# MCU_Schematic_Winterbreak.net
KiCad netlist of a schematic drawn in Altium Designer
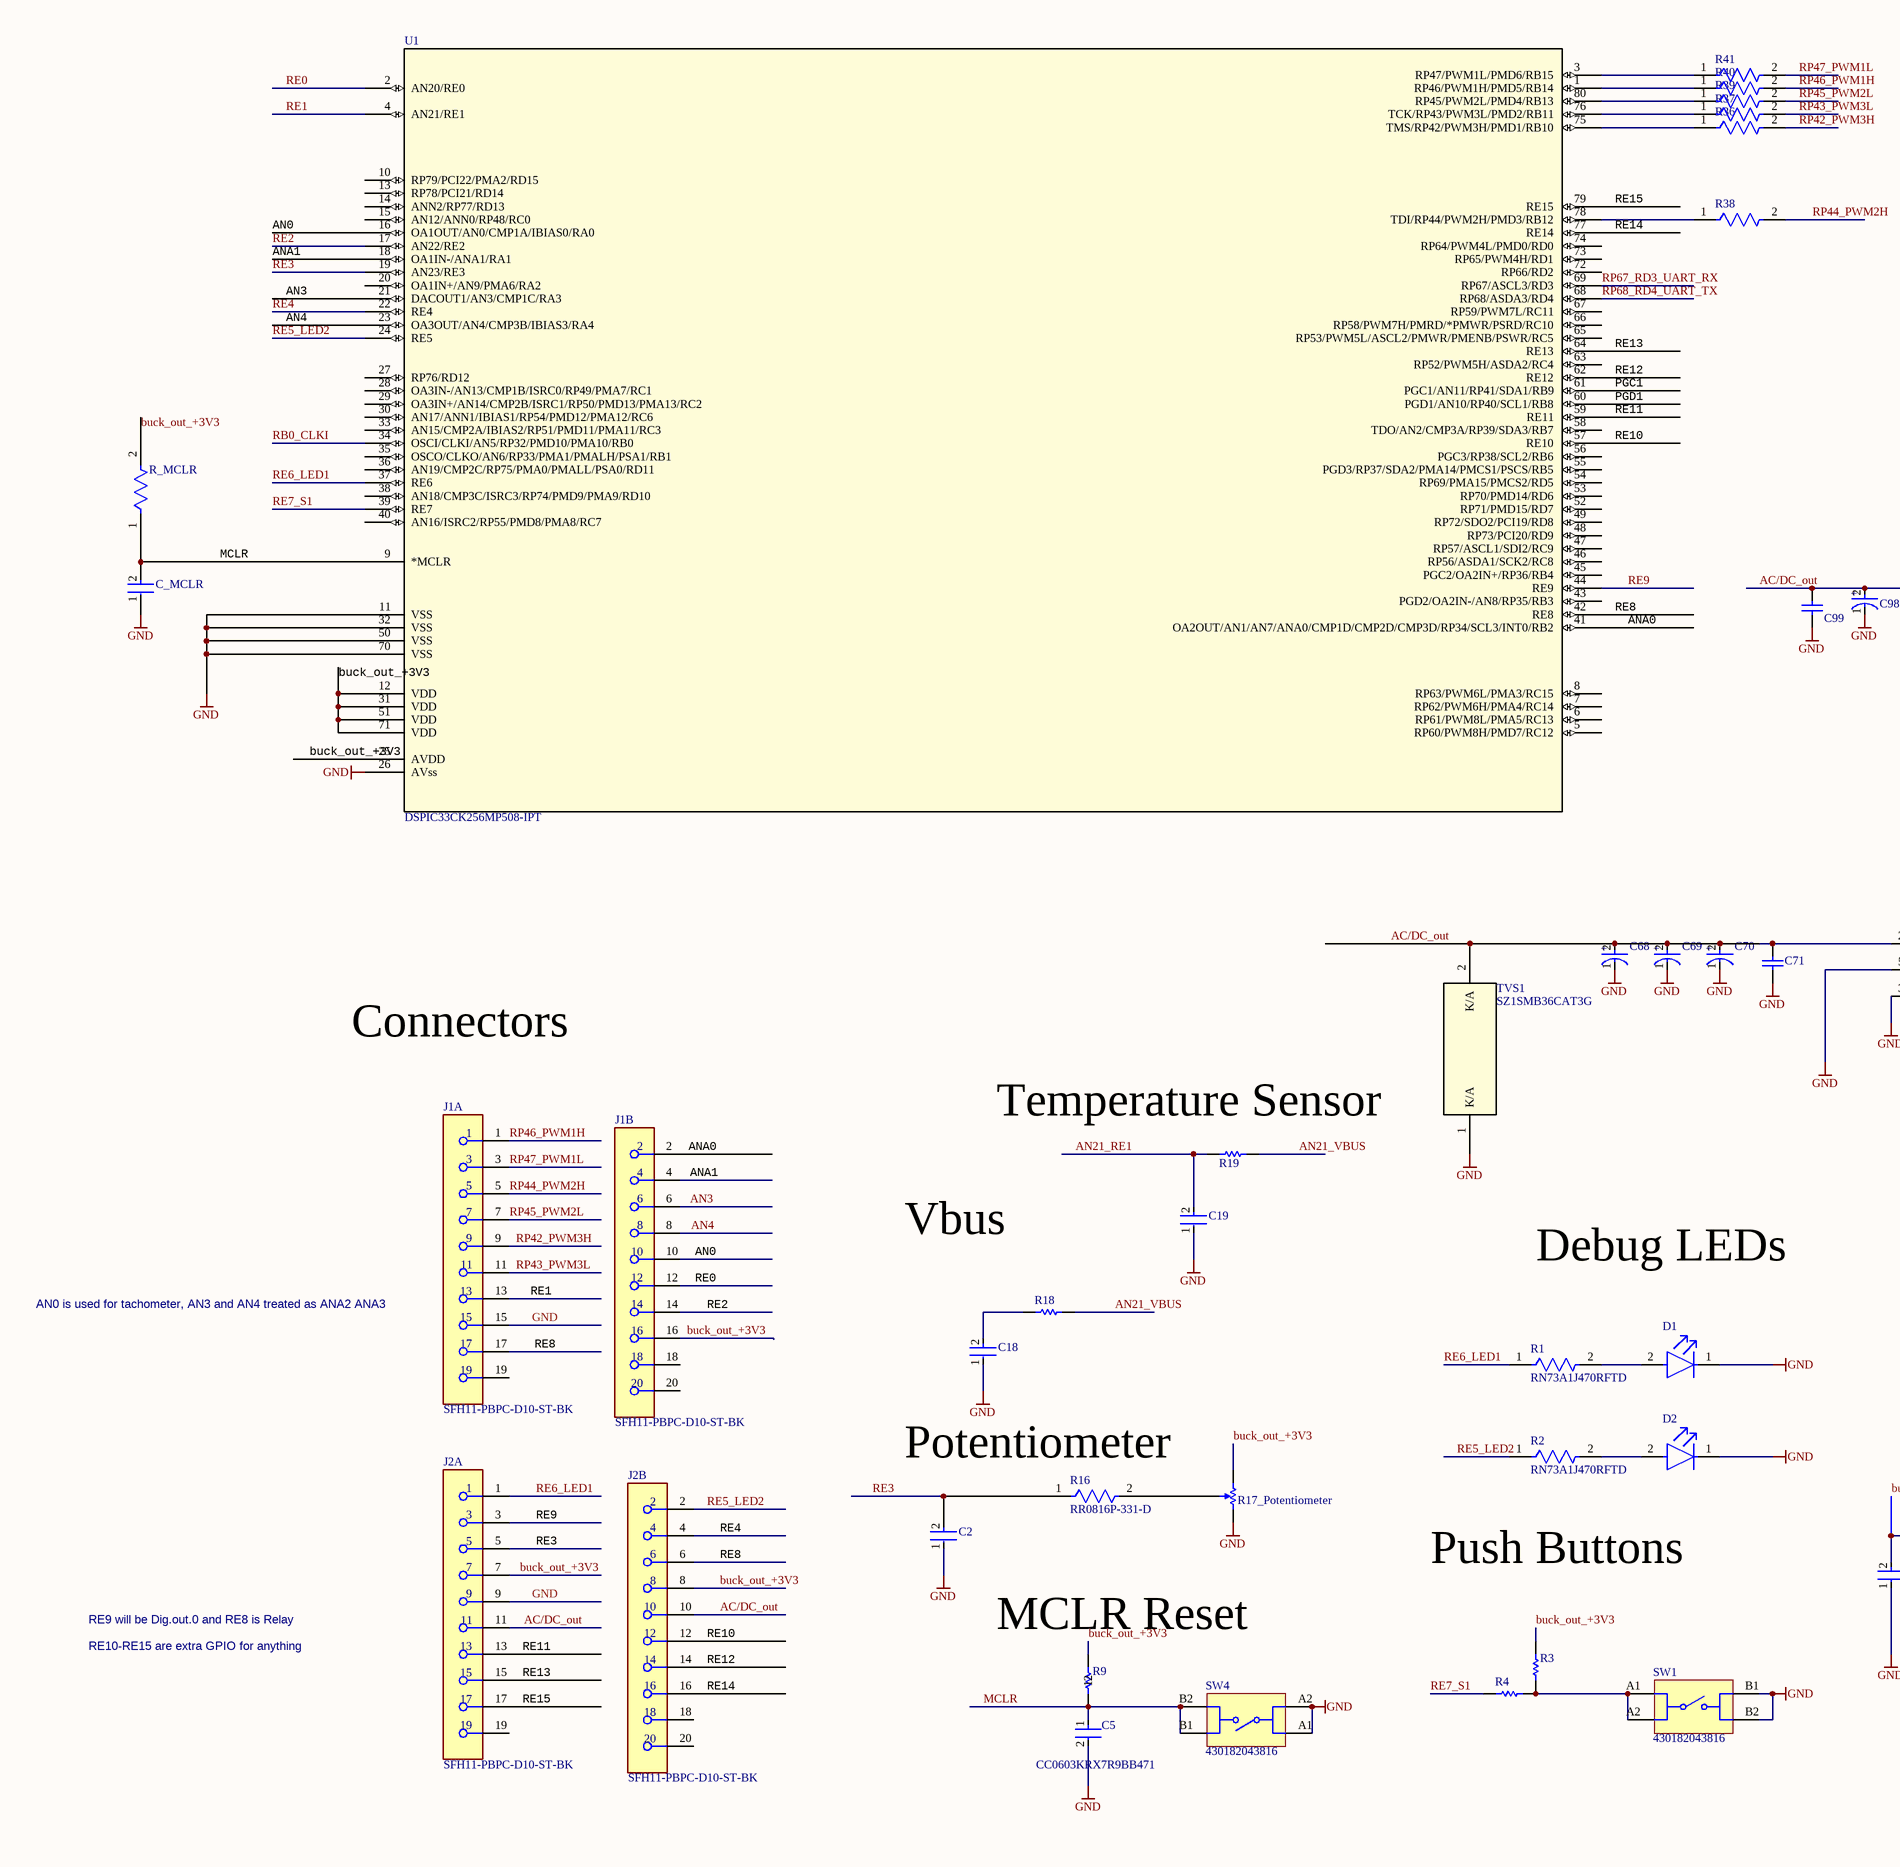
[diagram p0: MCU_Schematic_Winterbreak.SchDoc, left]
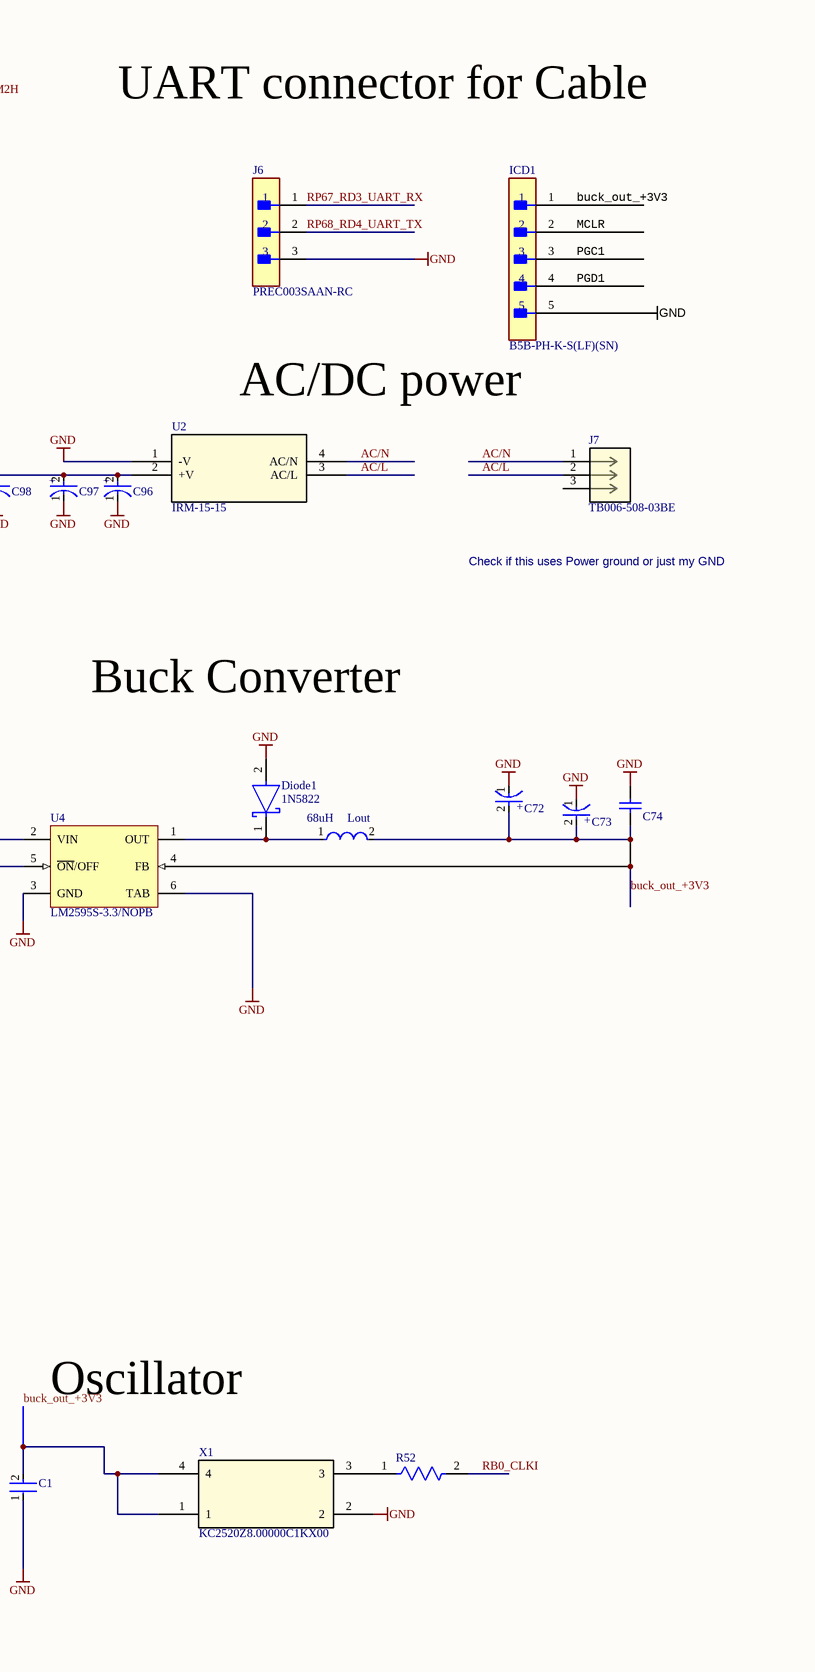
[diagram p1: MCU_Schematic_Winterbreak.SchDoc, right]

(export (version "E")
  (design (tool "Eeschema 10.0.6"))
  (components
    (comp (ref "C1")
      (value "GRM155R71C104KA88D")
      (footprint "FP-GRM15-MFG")
      (description "CAP CER 0.1UF 16V X7R 0402")
      (fields
        (field (name "TOLERANCE") "10%")
        (field (name "OCTOPART") "https://octopart.com/grm155r71c104ka88d-murata-196880")
      )
      (libsource (lib "Altium Content Vault") (part "236180d848d6139a670b325ea6854c9"))
    )
    (comp (ref "C2")
      (value "GRM155R71C104KA88D")
      (footprint "FP-GRM15-MFG")
      (description "CAP CER 0.1UF 16V X7R 0402")
      (fields
        (field (name "TOLERANCE") "10%")
        (field (name "OCTOPART") "https://octopart.com/grm155r71c104ka88d-murata-196880")
      )
      (libsource (lib "Altium Content Vault") (part "236180d848d6139a670b325ea6854c9"))
    )
    (comp (ref "C5")
      (value "CC0603KRX7R9BB471")
      (footprint "FP-CC0603-DA-MFG")
      (description "CAP CER 470PF 50V X7R 0603")
      (fields
        (field (name "VOLTAGE") "50 V")
        (field (name "OCTOPART") "https://octopart.com/cc0603krx7r9bb471-yageo-192931")
      )
      (libsource (lib "Altium Content Vault") (part "11868f565c42a9108669ba33697ecf6"))
    )
    (comp (ref "C18")
      (value "GRM155R71C104KA88D")
      (footprint "FP-GRM15-MFG")
      (description "CAP CER 0.1UF 16V X7R 0402")
      (fields
        (field (name "TOLERANCE") "10%")
        (field (name "OCTOPART") "https://octopart.com/grm155r71c104ka88d-murata-196880")
      )
      (libsource (lib "Altium Content Vault") (part "236180d848d6139a670b325ea6854c9"))
    )
    (comp (ref "C19")
      (value "GRM155R71C104KA88D")
      (footprint "FP-GRM15-MFG")
      (description "CAP CER 0.1UF 16V X7R 0402")
      (fields
        (field (name "TOLERANCE") "10%")
        (field (name "OCTOPART") "https://octopart.com/grm155r71c104ka88d-murata-196880")
      )
      (libsource (lib "Altium Content Vault") (part "236180d848d6139a670b325ea6854c9"))
    )
    (comp (ref "C68")
      (value "EEHAZS1H221B")
      (footprint "FP-EEHA-G16-MFG")
      (description "Conductive Polymer Hybrid Aluminum Electrolytic Capacitors 220uF ±20% 50V RADIAL TH 10x15.7mm")
      (libsource (lib "Altium Content Vault") (part "203bc49f2ac43e59fd269a8c329ed05"))
    )
    (comp (ref "C69")
      (value "EEHAZS1H221B")
      (footprint "FP-EEHA-G16-MFG")
      (description "Conductive Polymer Hybrid Aluminum Electrolytic Capacitors 220uF ±20% 50V RADIAL TH 10x15.7mm")
      (libsource (lib "Altium Content Vault") (part "203bc49f2ac43e59fd269a8c329ed05"))
    )
    (comp (ref "C70")
      (value "TAJE476K035RNJ")
      (footprint "FP-TAJE-MFG")
      (description "47uF 35V  ±10% 900mΩ 2917  SMD Tantalum Capacitor")
      (fields (field (name "VOLTAGE") "35V") (field (name "TOLERANCE") "10%"))
      (libsource (lib "Altium Content Vault") (part "203bc49f2ac43e59fd269a8c329ed05"))
    )
    (comp (ref "C71")
      (value "08055C104KAZ2A")
      (footprint "CAPC2013X94X50NL20T25")
      (fields (field (name "MANUFACTURER") "AVX Interconnect / Elco"))
      (libsource (lib "Altium Content Vault") (part "CAP"))
    )
    (comp (ref "C72")
      (value "EEHAZS1H221B")
      (footprint "FP-EEHA-G16-MFG")
      (description "Conductive Polymer Hybrid Aluminum Electrolytic Capacitors 220uF ±20% 50V RADIAL TH 10x15.7mm")
      (libsource (lib "Altium Content Vault") (part "203bc49f2ac43e59fd269a8c329ed05"))
    )
    (comp (ref "C73")
      (value "TAJE476K035RNJ")
      (footprint "FP-TAJE-MFG")
      (description "47uF 35V  ±10% 900mΩ 2917  SMD Tantalum Capacitor")
      (fields (field (name "VOLTAGE") "35V") (field (name "TOLERANCE") "10%"))
      (libsource (lib "Altium Content Vault") (part "203bc49f2ac43e59fd269a8c329ed05"))
    )
    (comp (ref "C74")
      (value "08055C104KAZ2A")
      (footprint "CAPC2013X94X50NL20T25")
      (fields (field (name "MANUFACTURER") "AVX Interconnect / Elco"))
      (libsource (lib "Altium Content Vault") (part "CAP"))
    )
    (comp (ref "C96")
      (value "EEHAZS1H221B")
      (footprint "FP-EEHA-G16-MFG")
      (description "Conductive Polymer Hybrid Aluminum Electrolytic Capacitors 220uF ±20% 50V RADIAL TH 10x15.7mm")
      (libsource (lib "Altium Content Vault") (part "203bc49f2ac43e59fd269a8c329ed05"))
    )
    (comp (ref "C97")
      (value "EEHAZS1H221B")
      (footprint "FP-EEHA-G16-MFG")
      (description "Conductive Polymer Hybrid Aluminum Electrolytic Capacitors 220uF ±20% 50V RADIAL TH 10x15.7mm")
      (libsource (lib "Altium Content Vault") (part "203bc49f2ac43e59fd269a8c329ed05"))
    )
    (comp (ref "C98")
      (value "TAJE476K035RNJ")
      (footprint "FP-TAJE-MFG")
      (description "47uF 35V  ±10% 900mΩ 2917  SMD Tantalum Capacitor")
      (fields (field (name "VOLTAGE") "35V") (field (name "TOLERANCE") "10%"))
      (libsource (lib "Altium Content Vault") (part "203bc49f2ac43e59fd269a8c329ed05"))
    )
    (comp (ref "C99")
      (value "08055C104KAZ2A")
      (footprint "CAPC2013X94X50NL20T25")
      (fields (field (name "MANUFACTURER") "AVX Interconnect / Elco"))
      (libsource (lib "Altium Content Vault") (part "CAP"))
    )
    (comp (ref "C_MCLR")
      (value "GRM155R71C104KA88D")
      (footprint "FP-GRM15-MFG")
      (description "CAP CER 0.1UF 16V X7R 0402")
      (fields
        (field (name "TOLERANCE") "10%")
        (field (name "OCTOPART") "https://octopart.com/grm155r71c104ka88d-murata-196880")
      )
      (libsource (lib "Altium Content Vault") (part "236180d848d6139a670b325ea6854c9"))
    )
    (comp (ref "D1")
      (value "LTST-C190KGKT")
      (footprint "FP-LTST-C190KGKT-MFG")
      (description "LED GREEN CLEAR CHIP SMD")
      (libsource (lib "Altium Content Vault") (part "8706943c75ba83719d021d2fdc84c58"))
    )
    (comp (ref "D2")
      (value "LTST-C190KGKT")
      (footprint "FP-LTST-C190KGKT-MFG")
      (description "LED GREEN CLEAR CHIP SMD")
      (libsource (lib "Altium Content Vault") (part "8706943c75ba83719d021d2fdc84c58"))
    )
    (comp (ref "Diode1")
      (value "1N5822")
      (footprint "FP-DO-201AD-MFG")
      (description "DIODE SCHOTTKY 40V 3A DO201AD")
      (fields
        (field (name "OCTOPART") "https://octopart.com/1n5822-stmicroelectronics-323225")
        (field (name "MANUFACTURER") "STMicroelectronics")
      )
      (libsource (lib "Altium Content Vault") (part "1d6ec82d83fb6aee721767c19dac4b9"))
    )
    (comp (ref "ICD1")
      (value "B5B-PH-K-S(LF)(SN)")
      (footprint "FP-B5B-PH-K-S_LF_SN-MFG")
      (description "CONN HEADER VERT 5POS 2MM")
      (libsource (lib "Altium Content Vault") (part "bf93c07fd2649a848d0ec8585582aab"))
    )
    (comp (ref "J1")
      (value "SFH11-PBPC-D10-ST-BK")
      (footprint "FP-SFH11-PBPC-D10-ST-BK-MFG")
      (description "CONN HDR 20POS 0.1 GOLD PCB")
      (libsource (lib "Altium Content Vault") (part "86e307fb827e6da12e54f1dde2f44ab"))
    )
    (comp (ref "J2")
      (value "SFH11-PBPC-D10-ST-BK")
      (footprint "FP-SFH11-PBPC-D10-ST-BK-MFG")
      (description "CONN HDR 20POS 0.1 GOLD PCB")
      (libsource (lib "Altium Content Vault") (part "86e307fb827e6da12e54f1dde2f44ab"))
    )
    (comp (ref "J6")
      (value "PREC003SAAN-RC")
      (footprint "FP-PREC003SAAN-RC-MFG")
      (description "PREC003SAAN-RC Conn Header Vert 3POS 2.54MM")
      (libsource (lib "Altium Content Vault") (part "0d3f023dd272f625e17a2be33dea85f"))
    )
    (comp (ref "J7")
      (value "TB006-508-03BE")
      (footprint "CONN3_TB006-508_CUD")
      (description "No Description Available")
      (libsource (lib "TB006-508-03BE") (part "TB006-508-03BE"))
    )
    (comp (ref "Lout")
      (value "NR6028T680M")
      (footprint "FP-NR6028-MFG")
      (description "SMD Power Inductors 68uH ±20% 0.76A 0.546Ω")
      (fields (field (name "TOLERANCE") "20%") (field (name "INDUCTANCE") "68uH"))
      (libsource (lib "Altium Content Vault") (part "725321dda6339637d4d059423bc1c3c"))
    )
    (comp (ref "R1")
      (value "RN73A1J470RFTD")
      (footprint "FP-RN731J-MFG")
      (description "42")
      (fields
        (field (name "MANUFACTURER") "TE Connectivity")
        (field (name "OCTOPART") "https://octopart.com/rn73a1j470rftd-te+connectivity-22740827")
      )
      (libsource (lib "Altium Content Vault") (part "1029c3af85768c4190bb7ad29bc67b5"))
    )
    (comp (ref "R2")
      (value "RN73A1J470RFTD")
      (footprint "FP-RN731J-MFG")
      (description "42")
      (fields
        (field (name "MANUFACTURER") "TE Connectivity")
        (field (name "OCTOPART") "https://octopart.com/rn73a1j470rftd-te+connectivity-22740827")
      )
      (libsource (lib "Altium Content Vault") (part "1029c3af85768c4190bb7ad29bc67b5"))
    )
    (comp (ref "R3")
      (value "ERJ3EKF1002V")
      (footprint "RESC1609X55X30LL15T15")
      (description "Chip Resistor, 10 KOhm, +/- 1%, 0.1 W, -55 to 155 degC, 0603 (1608 Metric), RoHS, Tape and Reel")
      (fields (field (name "TOLERANCE") "1%") (field (name "MANUFACTURER") "Panasonic"))
      (libsource (lib "") (part "RES-2_1"))
    )
    (comp (ref "R4")
      (value "ERJ-3EKF1001V")
      (footprint "RESC1608X55X30LL15T15")
      (fields (field (name "MANUFACTURER") "Panasonic"))
      (libsource (lib "Altium Content Vault") (part "RES"))
    )
    (comp (ref "R9")
      (value "ERJ3EKF1002V")
      (footprint "RESC1609X55X30LL15T15")
      (description "Chip Resistor, 10 KOhm, +/- 1%, 0.1 W, -55 to 155 degC, 0603 (1608 Metric), RoHS, Tape and Reel")
      (fields (field (name "TOLERANCE") "1%") (field (name "MANUFACTURER") "Panasonic"))
      (libsource (lib "Altium Content Vault") (part "RES-2"))
    )
    (comp (ref "R16")
      (value "RR0816P-331-D")
      (footprint "FP-RR0816-IPC_C")
      (description "330Ω ±0.5% 0.0625W 1/16W Chip Resistor 0603 (1608 Metric) Thin Film")
      (fields (field (name "TOLERANCE") "0.5%"))
      (libsource (lib "Altium Content Vault") (part "1029c3af85768c4190bb7ad29bc67b5"))
    )
    (comp (ref "R17_Potentiometer")
      (value "P090S-14T20BR10K")
      (footprint "RES-POT-3")
      (fields (field (name "TOLERANCE") "±20%") (field (name "MANUFACTURER") "BI Technologies"))
      (libsource (lib "Altium Content Vault") (part "RES-ADJ-3_A"))
    )
    (comp (ref "R18")
      (value "ERJ-3EKF1000V")
      (footprint "RESC1608X55X30LL15T15")
      (fields (field (name "MANUFACTURER") "Panasonic"))
      (libsource (lib "Altium Content Vault") (part "RES"))
    )
    (comp (ref "R19")
      (value "ERJ3EKF1002V")
      (footprint "RESC1609X55X30LL15T15")
      (description "Chip Resistor, 10 KOhm, +/- 1%, 0.1 W, -55 to 155 degC, 0603 (1608 Metric), RoHS, Tape and Reel")
      (fields (field (name "TOLERANCE") "1%") (field (name "MANUFACTURER") "Panasonic"))
      (libsource (lib "") (part "RES-2_1"))
    )
    (comp (ref "R36")
      (value "RR0816Q-750-D")
      (footprint "FP-RR0816-IPC_B")
      (description "75Ω ±0.5% 0.0625W 1/16W Chip Resistor 0603 (1608 Metric) Thin Film")
      (fields (field (name "TOLERANCE") "0.5%"))
      (libsource (lib "Altium Content Vault") (part "1029c3af85768c4190bb7ad29bc67b5"))
    )
    (comp (ref "R37")
      (value "RR0816Q-750-D")
      (footprint "FP-RR0816-IPC_B")
      (description "75Ω ±0.5% 0.0625W 1/16W Chip Resistor 0603 (1608 Metric) Thin Film")
      (fields (field (name "TOLERANCE") "0.5%"))
      (libsource (lib "Altium Content Vault") (part "1029c3af85768c4190bb7ad29bc67b5"))
    )
    (comp (ref "R38")
      (value "RR0816Q-750-D")
      (footprint "FP-RR0816-IPC_B")
      (description "75Ω ±0.5% 0.0625W 1/16W Chip Resistor 0603 (1608 Metric) Thin Film")
      (fields (field (name "TOLERANCE") "0.5%"))
      (libsource (lib "Altium Content Vault") (part "1029c3af85768c4190bb7ad29bc67b5"))
    )
    (comp (ref "R39")
      (value "RR0816Q-750-D")
      (footprint "FP-RR0816-IPC_B")
      (description "75Ω ±0.5% 0.0625W 1/16W Chip Resistor 0603 (1608 Metric) Thin Film")
      (fields (field (name "TOLERANCE") "0.5%"))
      (libsource (lib "Altium Content Vault") (part "1029c3af85768c4190bb7ad29bc67b5"))
    )
    (comp (ref "R40")
      (value "RR0816Q-750-D")
      (footprint "FP-RR0816-IPC_B")
      (description "75Ω ±0.5% 0.0625W 1/16W Chip Resistor 0603 (1608 Metric) Thin Film")
      (fields (field (name "TOLERANCE") "0.5%"))
      (libsource (lib "Altium Content Vault") (part "1029c3af85768c4190bb7ad29bc67b5"))
    )
    (comp (ref "R41")
      (value "RR0816Q-750-D")
      (footprint "FP-RR0816-IPC_B")
      (description "75Ω ±0.5% 0.0625W 1/16W Chip Resistor 0603 (1608 Metric) Thin Film")
      (fields (field (name "TOLERANCE") "0.5%"))
      (libsource (lib "Altium Content Vault") (part "1029c3af85768c4190bb7ad29bc67b5"))
    )
    (comp (ref "R52")
      (value "RR0816Q-750-D")
      (footprint "FP-RR0816-IPC_B")
      (description "75Ω ±0.5% 0.0625W 1/16W Chip Resistor 0603 (1608 Metric) Thin Film")
      (fields (field (name "TOLERANCE") "0.5%"))
      (libsource (lib "Altium Content Vault") (part "1029c3af85768c4190bb7ad29bc67b5"))
    )
    (comp (ref "R_MCLR")
      (value "ESR03EZPJ103")
      (footprint "FP-ESR03-IPC_C")
      (description "10kΩ ±5% 0.25W 0603 Anti-Surge Chip Resistor AEC-Q200")
      (fields (field (name "TOLERANCE") "5%"))
      (libsource (lib "Altium Content Vault") (part "1029c3af85768c4190bb7ad29bc67b5"))
    )
    (comp (ref "SW1")
      (value "430182043816")
      (footprint "430182043816")
      (description "Switch Tactile N.O. SPST Round Button Gull Wing 0.05A 12VDC 1000000Cycles 1.57N SMD Reel")
      (libsource (lib "") (part "SPST-NO_4P_1"))
    )
    (comp (ref "SW4")
      (value "430182043816")
      (footprint "430182043816")
      (description "Switch Tactile N.O. SPST Round Button Gull Wing 0.05A 12VDC 1000000Cycles 1.57N SMD Reel")
      (libsource (lib "Altium Content Vault") (part "SPST-NO_4P"))
    )
    (comp (ref "TVS1")
      (value "SZ1SMB36CAT3G")
      (footprint "SMB-2_4P60X3P95_ONS")
      (description "No Description Available")
      (libsource (lib "SZ1SMB36CAT3G") (part "SZ1SMB36CAT3G"))
    )
    (comp (ref "U1")
      (value "DSPIC33CK256MP508-IPT")
      (footprint "TQFP80_PT_MCH")
      (description "No Description Available")
      (libsource (lib "DSPIC33CK256MP508-IPT") (part "DSPIC33CK256MP508-IPT"))
    )
    (comp (ref "U2")
      (value "IRM-15-15")
      (footprint "IRM-15_MWU")
      (description "No Description Available")
      (libsource (lib "IRM-15-15") (part "IRM-15-15"))
    )
    (comp (ref "U4")
      (value "LM2595S-3.3/NOPB")
      (footprint "KTT0005B_N")
      (description "SIMPLE SWITCHER® Power Converter 150 KHz 1A Step-Down Voltage Regulator, 5-pin TO-263, Pb-Free")
      (fields (field (name "MANUFACTURER") "Texas Instruments"))
      (libsource (lib "Altium Content Vault") (part "PM-REG-LM2595S-12"))
    )
    (comp (ref "X1")
      (value "KC2520Z8.00000C1KX00")
      (footprint "OSC_0C1KX00_AVX")
      (description "No Description Available")
      (libsource (lib "KC2520Z8P00000C1KX00") (part "KC2520Z8.00000C1KX00"))
    )
  )
  (nets
    (net (code "1") (name "/AC{slash}DC_out") (class "Default")
      (node (ref "C68") (pin "2") (pinfunction "A_2") (pintype "passive"))
      (node (ref "C69") (pin "2") (pinfunction "A_2") (pintype "passive"))
      (node (ref "C70") (pin "2") (pinfunction "A_2") (pintype "passive"))
      (node (ref "C71") (pin "2") (pinfunction "2_2") (pintype "passive"))
      (node (ref "C96") (pin "2") (pinfunction "A_2") (pintype "passive"))
      (node (ref "C97") (pin "2") (pinfunction "A_2") (pintype "passive"))
      (node (ref "C98") (pin "2") (pinfunction "A_2") (pintype "passive"))
      (node (ref "C99") (pin "2") (pinfunction "2_2") (pintype "passive"))
      (node (ref "J2") (pin "10") (pinfunction "10_10") (pintype "passive"))
      (node (ref "J2") (pin "11") (pinfunction "11_11") (pintype "passive"))
      (node (ref "TVS1") (pin "2") (pinfunction "K/A_2") (pintype "passive"))
      (node (ref "U2") (pin "2") (pinfunction "+V_2") (pintype "power_in"))
      (node (ref "U4") (pin "2") (pinfunction "VIN_2") (pintype "power_in"))
    )
    (net (code "2") (name "/AC{slash}L") (class "Default")
      (node (ref "J7") (pin "2") (pinfunction "2_2") (pintype "passive"))
      (node (ref "U2") (pin "3") (pinfunction "AC/L_3") (pintype "passive"))
    )
    (net (code "3") (name "/AC{slash}N") (class "Default")
      (node (ref "J7") (pin "1") (pinfunction "1_1") (pintype "passive"))
      (node (ref "U2") (pin "4") (pinfunction "AC/N_4") (pintype "passive"))
    )
    (net (code "4") (name "/AN0") (class "Default")
      (node (ref "J1") (pin "10") (pinfunction "10_10") (pintype "passive"))
      (node (ref "U1") (pin "16") (pinfunction "OA1OUT/AN0/CMP1A/IBIAS0/RA0_16") (pintype "bidirectional"))
    )
    (net (code "5") (name "/AN3") (class "Default")
      (node (ref "J1") (pin "6") (pinfunction "6_6") (pintype "passive"))
      (node (ref "U1") (pin "21") (pinfunction "DACOUT1/AN3/CMP1C/RA3_21") (pintype "bidirectional"))
    )
    (net (code "6") (name "/AN4") (class "Default")
      (node (ref "J1") (pin "8") (pinfunction "8_8") (pintype "passive"))
      (node (ref "U1") (pin "23") (pinfunction "OA3OUT/AN4/CMP3B/IBIAS3/RA4_23") (pintype "bidirectional"))
    )
    (net (code "7") (name "/AN21_RE1") (class "Default")
      (node (ref "C19") (pin "2") (pinfunction "2_2") (pintype "passive"))
      (node (ref "R19") (pin "2") (pinfunction "2_2") (pintype "passive"))
    )
    (net (code "8") (name "/AN21_VBUS") (class "Default")
      (node (ref "R18") (pin "2") (pinfunction "2_2") (pintype "passive"))
      (node (ref "R19") (pin "1") (pinfunction "1_1") (pintype "passive"))
    )
    (net (code "9") (name "/ANA0") (class "Default")
      (node (ref "J1") (pin "2") (pinfunction "2_2") (pintype "passive"))
      (node (ref "U1") (pin "41") (pinfunction "OA2OUT/AN1/AN7/ANA0/CMP1D/CMP2D/CMP3D/RP34/SCL3/INT0/RB2_41") (pintype "bidirectional"))
    )
    (net (code "10") (name "/ANA1") (class "Default")
      (node (ref "J1") (pin "4") (pinfunction "4_4") (pintype "passive"))
      (node (ref "U1") (pin "18") (pinfunction "OA1IN-/ANA1/RA1_18") (pintype "bidirectional"))
    )
    (net (code "11") (name "/MCLR") (class "Default")
      (node (ref "C5") (pin "1") (pinfunction "1_1") (pintype "passive"))
      (node (ref "C_MCLR") (pin "2") (pinfunction "2_2") (pintype "passive"))
      (node (ref "ICD1") (pin "2") (pinfunction "2_2") (pintype "passive"))
      (node (ref "R9") (pin "1") (pinfunction "1_1") (pintype "passive"))
      (node (ref "R_MCLR") (pin "1") (pinfunction "1_1") (pintype "passive"))
      (node (ref "SW4") (pin "B1") (pinfunction "B1_B1") (pintype "passive"))
      (node (ref "SW4") (pin "B2") (pinfunction "B2_B2") (pintype "passive"))
      (node (ref "U1") (pin "9") (pinfunction "*MCLR_9") (pintype "passive"))
    )
    (net (code "12") (name "/PGC1") (class "Default")
      (node (ref "ICD1") (pin "3") (pinfunction "3_3") (pintype "passive"))
      (node (ref "U1") (pin "61") (pinfunction "PGC1/AN11/RP41/SDA1/RB9_61") (pintype "bidirectional"))
    )
    (net (code "13") (name "/PGD1") (class "Default")
      (node (ref "ICD1") (pin "4") (pinfunction "4_4") (pintype "passive"))
      (node (ref "U1") (pin "60") (pinfunction "PGD1/AN10/RP40/SCL1/RB8_60") (pintype "bidirectional"))
    )
    (net (code "14") (name "/RB0_CLKI") (class "Default")
      (node (ref "R52") (pin "2") (pinfunction "2_2") (pintype "passive"))
      (node (ref "U1") (pin "34") (pinfunction "OSCI/CLKI/AN5/RP32/PMD10/PMA10/RB0_34") (pintype "bidirectional"))
    )
    (net (code "15") (name "/RE0") (class "Default")
      (node (ref "J1") (pin "12") (pinfunction "12_12") (pintype "passive"))
      (node (ref "U1") (pin "2") (pinfunction "AN20/RE0_2") (pintype "bidirectional"))
    )
    (net (code "16") (name "/RE1") (class "Default")
      (node (ref "J1") (pin "13") (pinfunction "13_13") (pintype "passive"))
      (node (ref "U1") (pin "4") (pinfunction "AN21/RE1_4") (pintype "bidirectional"))
    )
    (net (code "17") (name "/RE2") (class "Default")
      (node (ref "J1") (pin "14") (pinfunction "14_14") (pintype "passive"))
      (node (ref "U1") (pin "17") (pinfunction "AN22/RE2_17") (pintype "bidirectional"))
    )
    (net (code "18") (name "/RE3") (class "Default")
      (node (ref "C2") (pin "2") (pinfunction "2_2") (pintype "passive"))
      (node (ref "J2") (pin "5") (pinfunction "5_5") (pintype "passive"))
      (node (ref "R16") (pin "1") (pinfunction "1_1") (pintype "passive"))
      (node (ref "U1") (pin "19") (pinfunction "AN23/RE3_19") (pintype "bidirectional"))
    )
    (net (code "19") (name "/RE4") (class "Default")
      (node (ref "J2") (pin "4") (pinfunction "4_4") (pintype "passive"))
      (node (ref "U1") (pin "22") (pinfunction "RE4_22") (pintype "bidirectional"))
    )
    (net (code "20") (name "/RE5_LED2") (class "Default")
      (node (ref "J2") (pin "2") (pinfunction "2_2") (pintype "passive"))
      (node (ref "R2") (pin "1") (pinfunction "1_1") (pintype "passive"))
      (node (ref "U1") (pin "24") (pinfunction "RE5_24") (pintype "bidirectional"))
    )
    (net (code "21") (name "/RE6_LED1") (class "Default")
      (node (ref "J2") (pin "1") (pinfunction "1_1") (pintype "passive"))
      (node (ref "R1") (pin "1") (pinfunction "1_1") (pintype "passive"))
      (node (ref "U1") (pin "37") (pinfunction "RE6_37") (pintype "bidirectional"))
    )
    (net (code "22") (name "/RE7_S1") (class "Default")
      (node (ref "R4") (pin "1") (pinfunction "1_1") (pintype "passive"))
      (node (ref "U1") (pin "39") (pinfunction "RE7_39") (pintype "bidirectional"))
    )
    (net (code "23") (name "/RE8") (class "Default")
      (node (ref "J1") (pin "17") (pinfunction "17_17") (pintype "passive"))
      (node (ref "J2") (pin "6") (pinfunction "6_6") (pintype "passive"))
      (node (ref "U1") (pin "42") (pinfunction "RE8_42") (pintype "bidirectional"))
    )
    (net (code "24") (name "/RE9") (class "Default")
      (node (ref "J2") (pin "3") (pinfunction "3_3") (pintype "passive"))
      (node (ref "U1") (pin "44") (pinfunction "RE9_44") (pintype "bidirectional"))
    )
    (net (code "25") (name "/RE10") (class "Default")
      (node (ref "J2") (pin "12") (pinfunction "12_12") (pintype "passive"))
      (node (ref "U1") (pin "57") (pinfunction "RE10_57") (pintype "bidirectional"))
    )
    (net (code "26") (name "/RE11") (class "Default")
      (node (ref "J2") (pin "13") (pinfunction "13_13") (pintype "passive"))
      (node (ref "U1") (pin "59") (pinfunction "RE11_59") (pintype "bidirectional"))
    )
    (net (code "27") (name "/RE12") (class "Default")
      (node (ref "J2") (pin "14") (pinfunction "14_14") (pintype "passive"))
      (node (ref "U1") (pin "62") (pinfunction "RE12_62") (pintype "bidirectional"))
    )
    (net (code "28") (name "/RE13") (class "Default")
      (node (ref "J2") (pin "15") (pinfunction "15_15") (pintype "passive"))
      (node (ref "U1") (pin "64") (pinfunction "RE13_64") (pintype "bidirectional"))
    )
    (net (code "29") (name "/RE14") (class "Default")
      (node (ref "J2") (pin "16") (pinfunction "16_16") (pintype "passive"))
      (node (ref "U1") (pin "77") (pinfunction "RE14_77") (pintype "bidirectional"))
    )
    (net (code "30") (name "/RE15") (class "Default")
      (node (ref "J2") (pin "17") (pinfunction "17_17") (pintype "passive"))
      (node (ref "U1") (pin "79") (pinfunction "RE15_79") (pintype "bidirectional"))
    )
    (net (code "31") (name "/RP42_PWM3H") (class "Default")
      (node (ref "J1") (pin "9") (pinfunction "9_9") (pintype "passive"))
      (node (ref "R36") (pin "2") (pinfunction "2_2") (pintype "passive"))
    )
    (net (code "32") (name "/RP43_PWM3L") (class "Default")
      (node (ref "J1") (pin "11") (pinfunction "11_11") (pintype "passive"))
      (node (ref "R37") (pin "2") (pinfunction "2_2") (pintype "passive"))
    )
    (net (code "33") (name "/RP44_PWM2H") (class "Default")
      (node (ref "J1") (pin "5") (pinfunction "5_5") (pintype "passive"))
      (node (ref "R38") (pin "2") (pinfunction "2_2") (pintype "passive"))
    )
    (net (code "34") (name "/RP45_PWM2L") (class "Default")
      (node (ref "J1") (pin "7") (pinfunction "7_7") (pintype "passive"))
      (node (ref "R39") (pin "2") (pinfunction "2_2") (pintype "passive"))
    )
    (net (code "35") (name "/RP46_PWM1H") (class "Default")
      (node (ref "J1") (pin "1") (pinfunction "1_1") (pintype "passive"))
      (node (ref "R40") (pin "2") (pinfunction "2_2") (pintype "passive"))
    )
    (net (code "36") (name "/RP47_PWM1L") (class "Default")
      (node (ref "J1") (pin "3") (pinfunction "3_3") (pintype "passive"))
      (node (ref "R41") (pin "2") (pinfunction "2_2") (pintype "passive"))
    )
    (net (code "37") (name "/RP67_RD3_UART_RX") (class "Default")
      (node (ref "J6") (pin "1") (pinfunction "1_1") (pintype "passive"))
      (node (ref "U1") (pin "69") (pinfunction "RP67/ASCL3/RD3_69") (pintype "bidirectional"))
    )
    (net (code "38") (name "/RP68_RD4_UART_TX") (class "Default")
      (node (ref "J6") (pin "2") (pinfunction "2_2") (pintype "passive"))
      (node (ref "U1") (pin "68") (pinfunction "RP68/ASDA3/RD4_68") (pintype "bidirectional"))
    )
    (net (code "39") (name "/buck_out_+3V3") (class "Default")
      (node (ref "C1") (pin "2") (pinfunction "2_2") (pintype "passive"))
      (node (ref "C72") (pin "2") (pinfunction "A_2") (pintype "passive"))
      (node (ref "C73") (pin "2") (pinfunction "A_2") (pintype "passive"))
      (node (ref "C74") (pin "2") (pinfunction "2_2") (pintype "passive"))
      (node (ref "ICD1") (pin "1") (pinfunction "1_1") (pintype "passive"))
      (node (ref "J1") (pin "16") (pinfunction "16_16") (pintype "passive"))
      (node (ref "J2") (pin "7") (pinfunction "7_7") (pintype "passive"))
      (node (ref "J2") (pin "8") (pinfunction "8_8") (pintype "passive"))
      (node (ref "Lout") (pin "2") (pinfunction "2_2") (pintype "passive"))
      (node (ref "R17_Potentiometer") (pin "1") (pinfunction "1_1") (pintype "passive"))
      (node (ref "R3") (pin "2") (pinfunction "2_2") (pintype "passive"))
      (node (ref "R9") (pin "2") (pinfunction "2_2") (pintype "passive"))
      (node (ref "R_MCLR") (pin "2") (pinfunction "2_2") (pintype "passive"))
      (node (ref "U1") (pin "12") (pinfunction "VDD_12") (pintype "power_in"))
      (node (ref "U1") (pin "25") (pinfunction "AVDD_25") (pintype "power_in"))
      (node (ref "U1") (pin "31") (pinfunction "VDD_31") (pintype "power_in"))
      (node (ref "U1") (pin "51") (pinfunction "VDD_51") (pintype "power_in"))
      (node (ref "U1") (pin "71") (pinfunction "VDD_71") (pintype "power_in"))
      (node (ref "U4") (pin "4") (pinfunction "FB_4") (pintype "input"))
      (node (ref "X1") (pin "1") (pinfunction "1_1") (pintype "passive"))
      (node (ref "X1") (pin "4") (pinfunction "4_4") (pintype "passive"))
    )
    (net (code "40") (name "GND") (class "Default")
      (node (ref "C1") (pin "1") (pinfunction "1_1") (pintype "passive"))
      (node (ref "C18") (pin "1") (pinfunction "1_1") (pintype "passive"))
      (node (ref "C19") (pin "1") (pinfunction "1_1") (pintype "passive"))
      (node (ref "C2") (pin "1") (pinfunction "1_1") (pintype "passive"))
      (node (ref "C5") (pin "2") (pinfunction "2_2") (pintype "passive"))
      (node (ref "C68") (pin "1") (pinfunction "C_1") (pintype "passive"))
      (node (ref "C69") (pin "1") (pinfunction "C_1") (pintype "passive"))
      (node (ref "C70") (pin "1") (pinfunction "C_1") (pintype "passive"))
      (node (ref "C71") (pin "1") (pinfunction "1_1") (pintype "passive"))
      (node (ref "C72") (pin "1") (pinfunction "C_1") (pintype "passive"))
      (node (ref "C73") (pin "1") (pinfunction "C_1") (pintype "passive"))
      (node (ref "C74") (pin "1") (pinfunction "1_1") (pintype "passive"))
      (node (ref "C96") (pin "1") (pinfunction "C_1") (pintype "passive"))
      (node (ref "C97") (pin "1") (pinfunction "C_1") (pintype "passive"))
      (node (ref "C98") (pin "1") (pinfunction "C_1") (pintype "passive"))
      (node (ref "C99") (pin "1") (pinfunction "1_1") (pintype "passive"))
      (node (ref "C_MCLR") (pin "1") (pinfunction "1_1") (pintype "passive"))
      (node (ref "D1") (pin "1") (pinfunction "C_1") (pintype "passive"))
      (node (ref "D2") (pin "1") (pinfunction "C_1") (pintype "passive"))
      (node (ref "Diode1") (pin "2") (pinfunction "A_2") (pintype "passive"))
      (node (ref "ICD1") (pin "5") (pinfunction "5_5") (pintype "passive"))
      (node (ref "J1") (pin "15") (pinfunction "15_15") (pintype "passive"))
      (node (ref "J2") (pin "9") (pinfunction "9_9") (pintype "passive"))
      (node (ref "J6") (pin "3") (pinfunction "3_3") (pintype "passive"))
      (node (ref "R17_Potentiometer") (pin "3") (pinfunction "3_3") (pintype "passive"))
      (node (ref "SW1") (pin "B1") (pinfunction "B1_B1") (pintype "passive"))
      (node (ref "SW1") (pin "B2") (pinfunction "B2_B2") (pintype "passive"))
      (node (ref "SW4") (pin "A1") (pinfunction "A1_A1") (pintype "passive"))
      (node (ref "SW4") (pin "A2") (pinfunction "A2_A2") (pintype "passive"))
      (node (ref "TVS1") (pin "1") (pinfunction "K/A_1") (pintype "passive"))
      (node (ref "U1") (pin "11") (pinfunction "VSS_11") (pintype "power_in"))
      (node (ref "U1") (pin "26") (pinfunction "AVss_26") (pintype "power_in"))
      (node (ref "U1") (pin "32") (pinfunction "VSS_32") (pintype "power_in"))
      (node (ref "U1") (pin "50") (pinfunction "VSS_50") (pintype "power_in"))
      (node (ref "U1") (pin "70") (pinfunction "VSS_70") (pintype "power_in"))
      (node (ref "U2") (pin "1") (pinfunction "-V_1") (pintype "power_in"))
      (node (ref "U4") (pin "3") (pinfunction "GND_3") (pintype "power_in"))
      (node (ref "U4") (pin "5") (pinfunction "~{ON}/OFF_5") (pintype "input"))
      (node (ref "U4") (pin "6") (pinfunction "TAB_6") (pintype "power_in"))
      (node (ref "X1") (pin "2") (pinfunction "2_2") (pintype "passive"))
    )
    (net (code "41") (name "Net-(C18-Pad2)") (class "Default")
      (node (ref "C18") (pin "2") (pinfunction "2_2") (pintype "passive"))
      (node (ref "R18") (pin "1") (pinfunction "1_1") (pintype "passive"))
    )
    (net (code "42") (name "Net-(D1-A)") (class "Default")
      (node (ref "D1") (pin "2") (pinfunction "A_2") (pintype "passive"))
      (node (ref "R1") (pin "2") (pinfunction "2_2") (pintype "passive"))
    )
    (net (code "43") (name "Net-(D2-A)") (class "Default")
      (node (ref "D2") (pin "2") (pinfunction "A_2") (pintype "passive"))
      (node (ref "R2") (pin "2") (pinfunction "2_2") (pintype "passive"))
    )
    (net (code "44") (name "Net-(Diode1-C)") (class "Default")
      (node (ref "Diode1") (pin "1") (pinfunction "C_1") (pintype "passive"))
      (node (ref "Lout") (pin "1") (pinfunction "1_1") (pintype "passive"))
      (node (ref "U4") (pin "1") (pinfunction "OUT_1") (pintype "power_in"))
    )
    (net (code "45") (name "Net-(R3-Pad1)") (class "Default")
      (node (ref "R3") (pin "1") (pinfunction "1_1") (pintype "passive"))
      (node (ref "R4") (pin "2") (pinfunction "2_2") (pintype "passive"))
      (node (ref "SW1") (pin "A1") (pinfunction "A1_A1") (pintype "passive"))
      (node (ref "SW1") (pin "A2") (pinfunction "A2_A2") (pintype "passive"))
    )
    (net (code "46") (name "Net-(R16-Pad2)") (class "Default")
      (node (ref "R16") (pin "2") (pinfunction "2_2") (pintype "passive"))
      (node (ref "R17_Potentiometer") (pin "2") (pinfunction "2_2") (pintype "passive"))
    )
    (net (code "47") (name "Net-(R52-Pad1)") (class "Default")
      (node (ref "R52") (pin "1") (pinfunction "1_1") (pintype "passive"))
      (node (ref "X1") (pin "3") (pinfunction "3_3") (pintype "passive"))
    )
    (net (code "48") (name "Net-(U1-RP45{slash}PWM2L{slash}PMD4{slash}RB13)") (class "Default")
      (node (ref "R39") (pin "1") (pinfunction "1_1") (pintype "passive"))
      (node (ref "U1") (pin "80") (pinfunction "RP45/PWM2L/PMD4/RB13_80") (pintype "bidirectional"))
    )
    (net (code "49") (name "Net-(U1-RP46{slash}PWM1H{slash}PMD5{slash}RB14)") (class "Default")
      (node (ref "R40") (pin "1") (pinfunction "1_1") (pintype "passive"))
      (node (ref "U1") (pin "1") (pinfunction "RP46/PWM1H/PMD5/RB14_1") (pintype "bidirectional"))
    )
    (net (code "50") (name "Net-(U1-RP47{slash}PWM1L{slash}PMD6{slash}RB15)") (class "Default")
      (node (ref "R41") (pin "1") (pinfunction "1_1") (pintype "passive"))
      (node (ref "U1") (pin "3") (pinfunction "RP47/PWM1L/PMD6/RB15_3") (pintype "bidirectional"))
    )
    (net (code "51") (name "Net-(U1-TCK{slash}RP43{slash}PWM3L{slash}PMD2{slash}RB11)") (class "Default")
      (node (ref "R37") (pin "1") (pinfunction "1_1") (pintype "passive"))
      (node (ref "U1") (pin "76") (pinfunction "TCK/RP43/PWM3L/PMD2/RB11_76") (pintype "bidirectional"))
    )
    (net (code "52") (name "Net-(U1-TDI{slash}RP44{slash}PWM2H{slash}PMD3{slash}RB12)") (class "Default")
      (node (ref "R38") (pin "1") (pinfunction "1_1") (pintype "passive"))
      (node (ref "U1") (pin "78") (pinfunction "TDI/RP44/PWM2H/PMD3/RB12_78") (pintype "bidirectional"))
    )
    (net (code "53") (name "Net-(U1-TMS{slash}RP42{slash}PWM3H{slash}PMD1{slash}RB10)") (class "Default")
      (node (ref "R36") (pin "1") (pinfunction "1_1") (pintype "passive"))
      (node (ref "U1") (pin "75") (pinfunction "TMS/RP42/PWM3H/PMD1/RB10_75") (pintype "bidirectional"))
    )
    (net (code "54") (name "unconnected-(J1-Pad18)") (class "Default")
      (node (ref "J1") (pin "18") (pinfunction "18_18") (pintype "passive"))
    )
    (net (code "55") (name "unconnected-(J1-Pad19)") (class "Default")
      (node (ref "J1") (pin "19") (pinfunction "19_19") (pintype "passive"))
    )
    (net (code "56") (name "unconnected-(J1-Pad20)") (class "Default")
      (node (ref "J1") (pin "20") (pinfunction "20_20") (pintype "passive"))
    )
    (net (code "57") (name "unconnected-(J2-Pad18)") (class "Default")
      (node (ref "J2") (pin "18") (pinfunction "18_18") (pintype "passive"))
    )
    (net (code "58") (name "unconnected-(J2-Pad19)") (class "Default")
      (node (ref "J2") (pin "19") (pinfunction "19_19") (pintype "passive"))
    )
    (net (code "59") (name "unconnected-(J2-Pad20)") (class "Default")
      (node (ref "J2") (pin "20") (pinfunction "20_20") (pintype "passive"))
    )
    (net (code "60") (name "unconnected-(J7-Pad3)") (class "Default")
      (node (ref "J7") (pin "3") (pinfunction "3_3") (pintype "passive"))
    )
    (net (code "61") (name "unconnected-(U1-AN12{slash}ANN0{slash}RP48{slash}RC0-Pad15)") (class "Default")
      (node (ref "U1") (pin "15") (pinfunction "AN12/ANN0/RP48/RC0_15") (pintype "bidirectional"))
    )
    (net (code "62") (name "unconnected-(U1-AN15{slash}CMP2A{slash}IBIAS2{slash}RP51{slash}PMD11{slash}PMA11{slash}RC3-Pad33)") (class "Default")
      (node (ref "U1") (pin "33") (pinfunction "AN15/CMP2A/IBIAS2/RP51/PMD11/PMA11/RC3_33") (pintype "bidirectional"))
    )
    (net (code "63") (name "unconnected-(U1-AN16{slash}ISRC2{slash}RP55{slash}PMD8{slash}PMA8{slash}RC7-Pad40)") (class "Default")
      (node (ref "U1") (pin "40") (pinfunction "AN16/ISRC2/RP55/PMD8/PMA8/RC7_40") (pintype "bidirectional"))
    )
    (net (code "64") (name "unconnected-(U1-AN17{slash}ANN1{slash}IBIAS1{slash}RP54{slash}PMD12{slash}PMA12{slash}RC6-Pad30)") (class "Default")
      (node (ref "U1") (pin "30") (pinfunction "AN17/ANN1/IBIAS1/RP54/PMD12/PMA12/RC6_30") (pintype "bidirectional"))
    )
    (net (code "65") (name "unconnected-(U1-AN18{slash}CMP3C{slash}ISRC3{slash}RP74{slash}PMD9{slash}PMA9{slash}RD10-Pad38)") (class "Default")
      (node (ref "U1") (pin "38") (pinfunction "AN18/CMP3C/ISRC3/RP74/PMD9/PMA9/RD10_38") (pintype "bidirectional"))
    )
    (net (code "66") (name "unconnected-(U1-AN19{slash}CMP2C{slash}RP75{slash}PMA0{slash}PMALL{slash}PSA0{slash}RD11-Pad36)") (class "Default")
      (node (ref "U1") (pin "36") (pinfunction "AN19/CMP2C/RP75/PMA0/PMALL/PSA0/RD11_36") (pintype "bidirectional"))
    )
    (net (code "67") (name "unconnected-(U1-ANN2{slash}RP77{slash}RD13-Pad14)") (class "Default")
      (node (ref "U1") (pin "14") (pinfunction "ANN2/RP77/RD13_14") (pintype "bidirectional"))
    )
    (net (code "68") (name "unconnected-(U1-OA1IN+{slash}AN9{slash}PMA6{slash}RA2-Pad20)") (class "Default")
      (node (ref "U1") (pin "20") (pinfunction "OA1IN+/AN9/PMA6/RA2_20") (pintype "bidirectional"))
    )
    (net (code "69") (name "unconnected-(U1-OA3IN+{slash}AN14{slash}CMP2B{slash}ISRC1{slash}RP50{slash}PMD13{slash}PMA13{slash}RC2-Pad29)") (class "Default")
      (node (ref "U1") (pin "29") (pinfunction "OA3IN+/AN14/CMP2B/ISRC1/RP50/PMD13/PMA13/RC2_29") (pintype "bidirectional"))
    )
    (net (code "70") (name "unconnected-(U1-OA3IN-{slash}AN13{slash}CMP1B{slash}ISRC0{slash}RP49{slash}PMA7{slash}RC1-Pad28)") (class "Default")
      (node (ref "U1") (pin "28") (pinfunction "OA3IN-/AN13/CMP1B/ISRC0/RP49/PMA7/RC1_28") (pintype "bidirectional"))
    )
    (net (code "71") (name "unconnected-(U1-OSCO{slash}CLKO{slash}AN6{slash}RP33{slash}PMA1{slash}PMALH{slash}PSA1{slash}RB1-Pad35)") (class "Default")
      (node (ref "U1") (pin "35") (pinfunction "OSCO/CLKO/AN6/RP33/PMA1/PMALH/PSA1/RB1_35") (pintype "bidirectional"))
    )
    (net (code "72") (name "unconnected-(U1-PGC2{slash}OA2IN+{slash}RP36{slash}RB4-Pad45)") (class "Default")
      (node (ref "U1") (pin "45") (pinfunction "PGC2/OA2IN+/RP36/RB4_45") (pintype "bidirectional"))
    )
    (net (code "73") (name "unconnected-(U1-PGC3{slash}RP38{slash}SCL2{slash}RB6-Pad56)") (class "Default")
      (node (ref "U1") (pin "56") (pinfunction "PGC3/RP38/SCL2/RB6_56") (pintype "bidirectional"))
    )
    (net (code "74") (name "unconnected-(U1-PGD2{slash}OA2IN-{slash}AN8{slash}RP35{slash}RB3-Pad43)") (class "Default")
      (node (ref "U1") (pin "43") (pinfunction "PGD2/OA2IN-/AN8/RP35/RB3_43") (pintype "bidirectional"))
    )
    (net (code "75") (name "unconnected-(U1-PGD3{slash}RP37{slash}SDA2{slash}PMA14{slash}PMCS1{slash}PSCS{slash}RB5-Pad55)") (class "Default")
      (node (ref "U1") (pin "55") (pinfunction "PGD3/RP37/SDA2/PMA14/PMCS1/PSCS/RB5_55") (pintype "bidirectional"))
    )
    (net (code "76") (name "unconnected-(U1-RP52{slash}PWM5H{slash}ASDA2{slash}RC4-Pad63)") (class "Default")
      (node (ref "U1") (pin "63") (pinfunction "RP52/PWM5H/ASDA2/RC4_63") (pintype "bidirectional"))
    )
    (net (code "77") (name "unconnected-(U1-RP53{slash}PWM5L{slash}ASCL2{slash}PMWR{slash}PMENB{slash}PSWR{slash}RC5-Pad65)") (class "Default")
      (node (ref "U1") (pin "65") (pinfunction "RP53/PWM5L/ASCL2/PMWR/PMENB/PSWR/RC5_65") (pintype "bidirectional"))
    )
    (net (code "78") (name "unconnected-(U1-RP56{slash}ASDA1{slash}SCK2{slash}RC8-Pad46)") (class "Default")
      (node (ref "U1") (pin "46") (pinfunction "RP56/ASDA1/SCK2/RC8_46") (pintype "bidirectional"))
    )
    (net (code "79") (name "unconnected-(U1-RP57{slash}ASCL1{slash}SDI2{slash}RC9-Pad47)") (class "Default")
      (node (ref "U1") (pin "47") (pinfunction "RP57/ASCL1/SDI2/RC9_47") (pintype "bidirectional"))
    )
    (net (code "80") (name "unconnected-(U1-RP58{slash}PWM7H{slash}PMRD{slash}*PMWR{slash}PSRD{slash}RC10-Pad66)") (class "Default")
      (node (ref "U1") (pin "66") (pinfunction "RP58/PWM7H/PMRD/*PMWR/PSRD/RC10_66") (pintype "bidirectional"))
    )
    (net (code "81") (name "unconnected-(U1-RP59{slash}PWM7L{slash}RC11-Pad67)") (class "Default")
      (node (ref "U1") (pin "67") (pinfunction "RP59/PWM7L/RC11_67") (pintype "bidirectional"))
    )
    (net (code "82") (name "unconnected-(U1-RP60{slash}PWM8H{slash}PMD7{slash}RC12-Pad5)") (class "Default")
      (node (ref "U1") (pin "5") (pinfunction "RP60/PWM8H/PMD7/RC12_5") (pintype "bidirectional"))
    )
    (net (code "83") (name "unconnected-(U1-RP61{slash}PWM8L{slash}PMA5{slash}RC13-Pad6)") (class "Default")
      (node (ref "U1") (pin "6") (pinfunction "RP61/PWM8L/PMA5/RC13_6") (pintype "bidirectional"))
    )
    (net (code "84") (name "unconnected-(U1-RP62{slash}PWM6H{slash}PMA4{slash}RC14-Pad7)") (class "Default")
      (node (ref "U1") (pin "7") (pinfunction "RP62/PWM6H/PMA4/RC14_7") (pintype "bidirectional"))
    )
    (net (code "85") (name "unconnected-(U1-RP63{slash}PWM6L{slash}PMA3{slash}RC15-Pad8)") (class "Default")
      (node (ref "U1") (pin "8") (pinfunction "RP63/PWM6L/PMA3/RC15_8") (pintype "bidirectional"))
    )
    (net (code "86") (name "unconnected-(U1-RP64{slash}PWM4L{slash}PMD0{slash}RD0-Pad74)") (class "Default")
      (node (ref "U1") (pin "74") (pinfunction "RP64/PWM4L/PMD0/RD0_74") (pintype "bidirectional"))
    )
    (net (code "87") (name "unconnected-(U1-RP65{slash}PWM4H{slash}RD1-Pad73)") (class "Default")
      (node (ref "U1") (pin "73") (pinfunction "RP65/PWM4H/RD1_73") (pintype "bidirectional"))
    )
    (net (code "88") (name "unconnected-(U1-RP66{slash}RD2-Pad72)") (class "Default")
      (node (ref "U1") (pin "72") (pinfunction "RP66/RD2_72") (pintype "bidirectional"))
    )
    (net (code "89") (name "unconnected-(U1-RP69{slash}PMA15{slash}PMCS2{slash}RD5-Pad54)") (class "Default")
      (node (ref "U1") (pin "54") (pinfunction "RP69/PMA15/PMCS2/RD5_54") (pintype "bidirectional"))
    )
    (net (code "90") (name "unconnected-(U1-RP70{slash}PMD14{slash}RD6-Pad53)") (class "Default")
      (node (ref "U1") (pin "53") (pinfunction "RP70/PMD14/RD6_53") (pintype "bidirectional"))
    )
    (net (code "91") (name "unconnected-(U1-RP71{slash}PMD15{slash}RD7-Pad52)") (class "Default")
      (node (ref "U1") (pin "52") (pinfunction "RP71/PMD15/RD7_52") (pintype "bidirectional"))
    )
    (net (code "92") (name "unconnected-(U1-RP72{slash}SDO2{slash}PCI19{slash}RD8-Pad49)") (class "Default")
      (node (ref "U1") (pin "49") (pinfunction "RP72/SDO2/PCI19/RD8_49") (pintype "bidirectional"))
    )
    (net (code "93") (name "unconnected-(U1-RP73{slash}PCI20{slash}RD9-Pad48)") (class "Default")
      (node (ref "U1") (pin "48") (pinfunction "RP73/PCI20/RD9_48") (pintype "bidirectional"))
    )
    (net (code "94") (name "unconnected-(U1-RP76{slash}RD12-Pad27)") (class "Default")
      (node (ref "U1") (pin "27") (pinfunction "RP76/RD12_27") (pintype "bidirectional"))
    )
    (net (code "95") (name "unconnected-(U1-RP78{slash}PCI21{slash}RD14-Pad13)") (class "Default")
      (node (ref "U1") (pin "13") (pinfunction "RP78/PCI21/RD14_13") (pintype "bidirectional"))
    )
    (net (code "96") (name "unconnected-(U1-RP79{slash}PCI22{slash}PMA2{slash}RD15-Pad10)") (class "Default")
      (node (ref "U1") (pin "10") (pinfunction "RP79/PCI22/PMA2/RD15_10") (pintype "bidirectional"))
    )
    (net (code "97") (name "unconnected-(U1-TDO{slash}AN2{slash}CMP3A{slash}RP39{slash}SDA3{slash}RB7-Pad58)") (class "Default")
      (node (ref "U1") (pin "58") (pinfunction "TDO/AN2/CMP3A/RP39/SDA3/RB7_58") (pintype "bidirectional"))
    )
  )
)
